# TK512_Optisk_Mottaker.net
KiCad netlist of a schematic drawn in Altium Designer
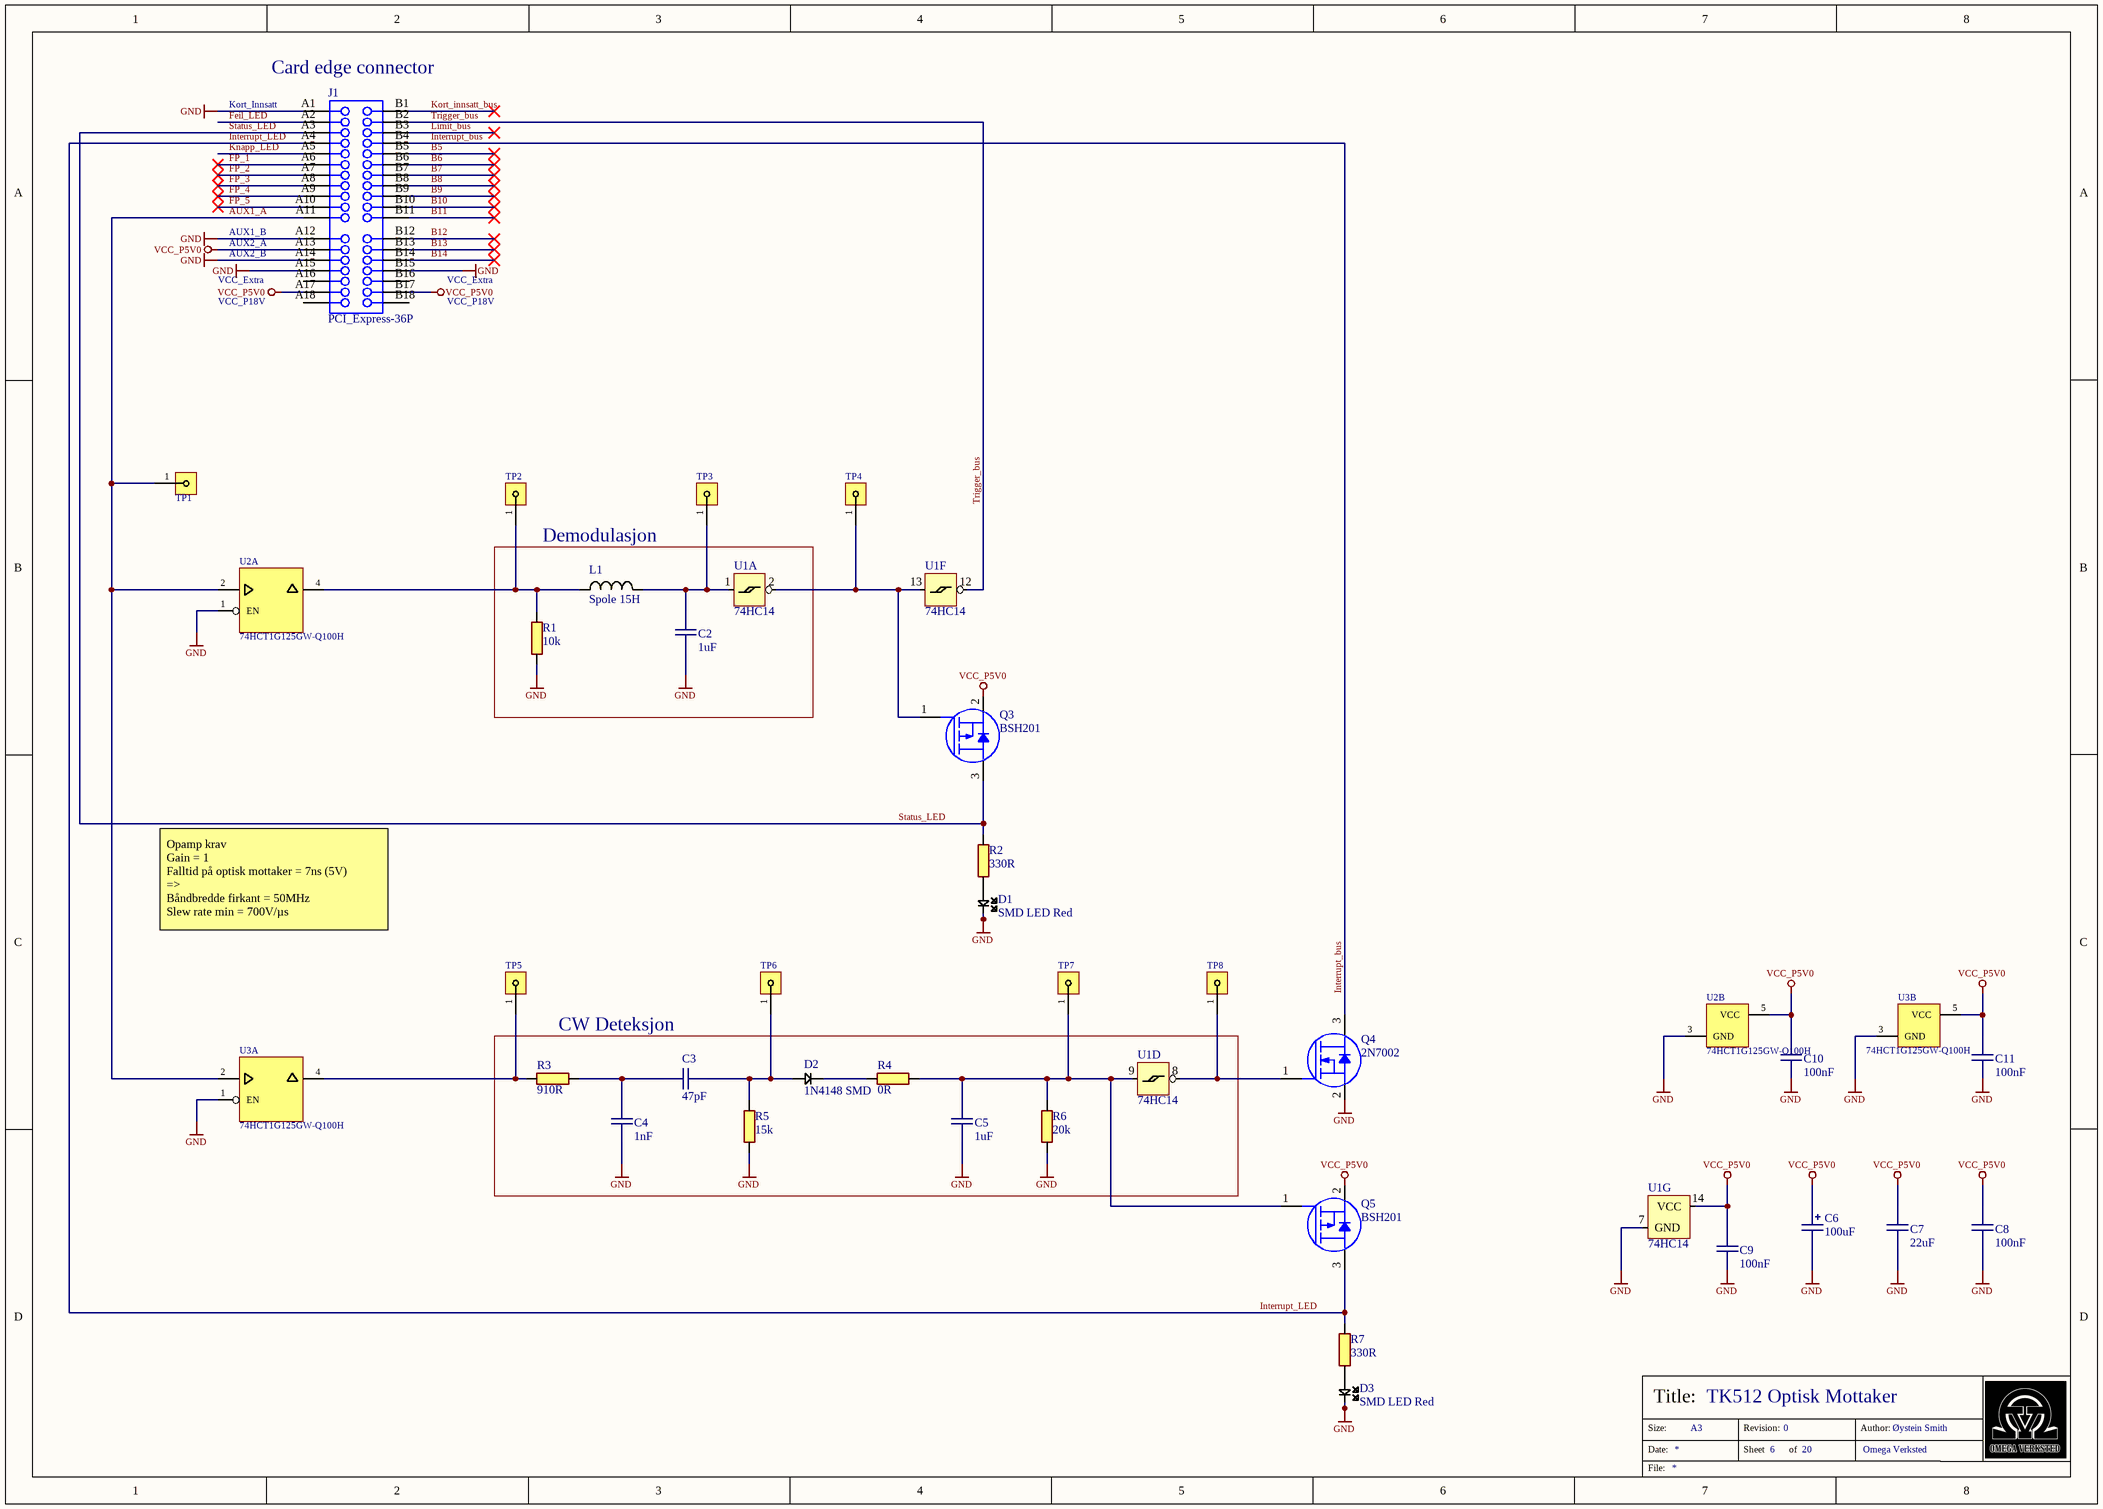
[diagram p0: TK512_Optisk_Mottaker.SchDoc]

(export (version "E")
  (design (tool "Eeschema 10.0.6"))
  (components
    (comp (ref "C2")
      (value "1uF")
      (footprint "CAPC1206(3216)170_N")
      (description "X7R 50V")
      (libsource (lib "OVLib_64") (part "CAP"))
    )
    (comp (ref "C3")
      (value "47pF")
      (footprint "CAPC0603(1608)55_N")
      (description "NP0 50V 5%")
      (libsource (lib "OVLib_64") (part "CAP"))
    )
    (comp (ref "C4")
      (value "1nF")
      (footprint "CAPC0603(1608)55_N")
      (description "X7R 50V 5%")
      (libsource (lib "OVLib_64") (part "CAP"))
    )
    (comp (ref "C5")
      (value "1uF")
      (footprint "CAPC0805(2012)100_N")
      (description "X7R 50V 10%")
      (libsource (lib "OVLib_64") (part "CAP"))
    )
    (comp (ref "C6")
      (value "100uF")
      (footprint "CAPPR25D06H11")
      (description "25V 2.5mm pitch")
      (libsource (lib "OVLib_64") (part "POLCAP"))
    )
    (comp (ref "C7")
      (value "22uF")
      (footprint "CAPC1206(3216)170_N")
      (description "10V 10% Tantalum")
      (libsource (lib "OVLib_64") (part "CAP"))
    )
    (comp (ref "C8")
      (value "100nF")
      (footprint "CAPC0603(1608)55_N")
      (description "X7R 50V 5%")
      (libsource (lib "OVLib_64") (part "CAP"))
    )
    (comp (ref "C9")
      (value "100nF")
      (footprint "CAPC0603(1608)55_N")
      (description "X7R 50V 5%")
      (libsource (lib "OVLib_64") (part "CAP"))
    )
    (comp (ref "C10")
      (value "100nF")
      (footprint "CAPC0603(1608)55_N")
      (description "X7R 50V 5%")
      (libsource (lib "OVLib_64") (part "CAP"))
    )
    (comp (ref "C11")
      (value "100nF")
      (footprint "CAPC0603(1608)55_N")
      (description "X7R 50V 5%")
      (libsource (lib "OVLib_64") (part "CAP"))
    )
    (comp (ref "D1")
      (value "SMD LED Red")
      (footprint "I_LEDC0603(1608)_N")
      (description "SMD")
      (libsource (lib "OVLib_64") (part "LED"))
    )
    (comp (ref "D2")
      (value "1N4148 SMD")
      (footprint "SOD123")
      (description "SMD signaldiode")
      (libsource (lib "OVLib_64") (part "Diode"))
    )
    (comp (ref "D3")
      (value "SMD LED Red")
      (footprint "I_LEDC0603(1608)_N")
      (description "SMD")
      (libsource (lib "OVLib_64") (part "LED"))
    )
    (comp (ref "J1")
      (value "PCI_Express-36P")
      (footprint "PCIeX1-GF-2D-1000-1K-O36")
      (description "PCI express PCB kortkankonnektor")
      (libsource (lib "OVLib_64") (part "PCI_Express-36P"))
    )
    (comp (ref "L1")
      (value "Spole 15H")
      (footprint "INDP3225X20N")
      (description "Wirewound Inductor, 15 µH, 2.8 ohm, 20 MHz, 130 mA")
      (libsource (lib "OVLib_64") (part "IND_GENERIC"))
    )
    (comp (ref "Q3")
      (value "BSH201")
      (footprint "SOT23-3_N")
      (description "P-Channel MOSFET 300mA")
      (libsource (lib "OVLib_64") (part "MOSFET_P_GSD"))
    )
    (comp (ref "Q4")
      (value "2N7002")
      (footprint "SOT323_N")
      (description "N-Channel MOSFET 300mA")
      (libsource (lib "OVLib_64") (part "MOSFET_N_GSD"))
    )
    (comp (ref "Q5")
      (value "BSH201")
      (footprint "SOT23-3_N")
      (description "P-Channel MOSFET 300mA")
      (libsource (lib "OVLib_64") (part "MOSFET_P_GSD"))
    )
    (comp (ref "R1")
      (value "10k")
      (footprint "RESC0603(1608)_N")
      (description "0.1W 1% Thick film resistor")
      (libsource (lib "") (part "Resistor2_2"))
    )
    (comp (ref "R2")
      (value "330R")
      (footprint "RESC0603(1608)_N")
      (description "0.1W 1% Thick film resistor")
      (libsource (lib "OVLib_64") (part "Resistor2"))
    )
    (comp (ref "R3")
      (value "910R")
      (footprint "RESC0603(1608)_N")
      (description "0.1W 1% Thick film resistor")
      (libsource (lib "") (part "Resistor2_1"))
    )
    (comp (ref "R4")
      (value "0R")
      (footprint "RESC0603(1608)_N")
      (description "0.1W 1% Thick film resistor, Jumper")
      (libsource (lib "") (part "Resistor2_1"))
    )
    (comp (ref "R5")
      (value "15k")
      (footprint "RESC0603(1608)_N")
      (description "0.1W 1% Thick film resistor")
      (libsource (lib "OVLib_64") (part "Resistor2"))
    )
    (comp (ref "R6")
      (value "20k")
      (footprint "RESC0603(1608)_N")
      (description "0.1W 1% Thick film resistor")
      (libsource (lib "OVLib_64") (part "Resistor2"))
    )
    (comp (ref "R7")
      (value "330R")
      (footprint "RESC0603(1608)_N")
      (description "0.1W 1% Thick film resistor")
      (libsource (lib "OVLib_64") (part "Resistor2"))
    )
    (comp (ref "TP1")
      (value "Header1x1")
      (footprint "HDRV1W64P254_1X1_254X254X900B")
      (description "2,54mm pitch")
      (libsource (lib "") (part "Header1x1_1"))
    )
    (comp (ref "TP2")
      (value "Header1x1")
      (footprint "HDRV1W64P254_1X1_254X254X900B")
      (description "2,54mm pitch")
      (libsource (lib "OVLib_64") (part "Header1x1"))
    )
    (comp (ref "TP3")
      (value "Header1x1")
      (footprint "HDRV1W64P254_1X1_254X254X900B")
      (description "2,54mm pitch")
      (libsource (lib "OVLib_64") (part "Header1x1"))
    )
    (comp (ref "TP4")
      (value "Header1x1")
      (footprint "HDRV1W64P254_1X1_254X254X900B")
      (description "2,54mm pitch")
      (libsource (lib "OVLib_64") (part "Header1x1"))
    )
    (comp (ref "TP5")
      (value "Header1x1")
      (footprint "HDRV1W64P254_1X1_254X254X900B")
      (description "2,54mm pitch")
      (libsource (lib "OVLib_64") (part "Header1x1"))
    )
    (comp (ref "TP6")
      (value "Header1x1")
      (footprint "HDRV1W64P254_1X1_254X254X900B")
      (description "2,54mm pitch")
      (libsource (lib "OVLib_64") (part "Header1x1"))
    )
    (comp (ref "TP7")
      (value "Header1x1")
      (footprint "HDRV1W64P254_1X1_254X254X900B")
      (description "2,54mm pitch")
      (libsource (lib "OVLib_64") (part "Header1x1"))
    )
    (comp (ref "TP8")
      (value "Header1x1")
      (footprint "HDRV1W64P254_1X1_254X254X900B")
      (description "2,54mm pitch")
      (libsource (lib "OVLib_64") (part "Header1x1"))
    )
    (comp (ref "U1")
      (value "74HC14")
      (footprint "SOIC-14")
      (description "Hex Schmitt trigger")
      (libsource (lib "OVLib_64") (part "6XSchmidt-Trigger"))
    )
    (comp (ref "U2")
      (value "74HCT1G125GW-Q100H")
      (footprint "SOT95P285X110-5N")
      (description "Buffer / Line Driver, 74HCT1G125, 4.5 V to 5.5 V, TSSOP-5")
      (libsource (lib "OVLib_64") (part "74HC1G125-Q100"))
    )
    (comp (ref "U3")
      (value "74HCT1G125GW-Q100H")
      (footprint "SOT95P285X110-5N")
      (description "Buffer / Line Driver, 74HCT1G125, 4.5 V to 5.5 V, TSSOP-5")
      (libsource (lib "OVLib_64") (part "74HC1G125-Q100"))
    )
  )
  (nets
    (net (code "1") (name "/AUX1_A") (class "Default")
      (node (ref "J1") (pin "A11") (pinfunction "A11_A11") (pintype "passive"))
      (node (ref "TP1") (pin "1") (pinfunction "1_1") (pintype "passive"))
      (node (ref "U2") (pin "2") (pinfunction "IN_2") (pintype "passive"))
      (node (ref "U3") (pin "2") (pinfunction "IN_2") (pintype "passive"))
    )
    (net (code "2") (name "/B5") (class "Default")
      (node (ref "J1") (pin "B5") (pinfunction "B5_B5") (pintype "passive+no_connect"))
    )
    (net (code "3") (name "/B6") (class "Default")
      (node (ref "J1") (pin "B6") (pinfunction "B6_B6") (pintype "passive+no_connect"))
    )
    (net (code "4") (name "/B7") (class "Default")
      (node (ref "J1") (pin "B7") (pinfunction "B7_B7") (pintype "passive+no_connect"))
    )
    (net (code "5") (name "/B8") (class "Default")
      (node (ref "J1") (pin "B8") (pinfunction "B8_B8") (pintype "passive+no_connect"))
    )
    (net (code "6") (name "/B9") (class "Default")
      (node (ref "J1") (pin "B9") (pinfunction "B9_B9") (pintype "passive+no_connect"))
    )
    (net (code "7") (name "/B10") (class "Default")
      (node (ref "J1") (pin "B10") (pinfunction "B10_B10") (pintype "passive+no_connect"))
    )
    (net (code "8") (name "/B11") (class "Default")
      (node (ref "J1") (pin "B11") (pinfunction "B11_B11") (pintype "passive+no_connect"))
    )
    (net (code "9") (name "/B12") (class "Default")
      (node (ref "J1") (pin "B12") (pinfunction "B12_B12") (pintype "passive+no_connect"))
    )
    (net (code "10") (name "/B13") (class "Default")
      (node (ref "J1") (pin "B13") (pinfunction "B13_B13") (pintype "passive+no_connect"))
    )
    (net (code "11") (name "/B14") (class "Default")
      (node (ref "J1") (pin "B14") (pinfunction "B14_B14") (pintype "passive+no_connect"))
    )
    (net (code "12") (name "/FP_1") (class "Default")
      (node (ref "J1") (pin "A6") (pinfunction "A6_A6") (pintype "passive+no_connect"))
    )
    (net (code "13") (name "/FP_2") (class "Default")
      (node (ref "J1") (pin "A7") (pinfunction "A7_A7") (pintype "passive+no_connect"))
    )
    (net (code "14") (name "/FP_3") (class "Default")
      (node (ref "J1") (pin "A8") (pinfunction "A8_A8") (pintype "passive+no_connect"))
    )
    (net (code "15") (name "/FP_4") (class "Default")
      (node (ref "J1") (pin "A9") (pinfunction "A9_A9") (pintype "passive+no_connect"))
    )
    (net (code "16") (name "/FP_5") (class "Default")
      (node (ref "J1") (pin "A10") (pinfunction "A10_A10") (pintype "passive+no_connect"))
    )
    (net (code "17") (name "/Feil_LED") (class "Default")
      (node (ref "J1") (pin "A2") (pinfunction "A2_A2") (pintype "passive"))
    )
    (net (code "18") (name "/Interrupt_LED") (class "Default")
      (node (ref "J1") (pin "A4") (pinfunction "A4_A4") (pintype "passive"))
      (node (ref "Q5") (pin "3") (pinfunction "Drain_3") (pintype "passive"))
      (node (ref "R7") (pin "2") (pinfunction "2_2") (pintype "passive"))
    )
    (net (code "19") (name "/Interrupt_bus") (class "Default")
      (node (ref "J1") (pin "B4") (pinfunction "B4_B4") (pintype "passive"))
      (node (ref "Q4") (pin "3") (pinfunction "Drain_3") (pintype "passive"))
    )
    (net (code "20") (name "/Knapp_LED") (class "Default")
      (node (ref "J1") (pin "A5") (pinfunction "A5_A5") (pintype "passive"))
    )
    (net (code "21") (name "/Kort_innsatt_bus") (class "Default")
      (node (ref "J1") (pin "B1") (pinfunction "B1_B1") (pintype "passive+no_connect"))
    )
    (net (code "22") (name "/Limit_bus") (class "Default")
      (node (ref "J1") (pin "B3") (pinfunction "B3_B3") (pintype "passive+no_connect"))
    )
    (net (code "23") (name "/Status_LED") (class "Default")
      (node (ref "J1") (pin "A3") (pinfunction "A3_A3") (pintype "passive"))
      (node (ref "Q3") (pin "3") (pinfunction "Drain_3") (pintype "passive"))
      (node (ref "R2") (pin "2") (pinfunction "2_2") (pintype "passive"))
    )
    (net (code "24") (name "/Trigger_bus") (class "Default")
      (node (ref "J1") (pin "B2") (pinfunction "B2_B2") (pintype "passive"))
      (node (ref "U1") (pin "12") (pinfunction "12_12") (pintype "passive"))
    )
    (net (code "25") (name "GND") (class "Default")
      (node (ref "C10") (pin "1") (pinfunction "1_1") (pintype "passive"))
      (node (ref "C11") (pin "1") (pinfunction "1_1") (pintype "passive"))
      (node (ref "C2") (pin "1") (pinfunction "1_1") (pintype "passive"))
      (node (ref "C4") (pin "1") (pinfunction "1_1") (pintype "passive"))
      (node (ref "C5") (pin "1") (pinfunction "1_1") (pintype "passive"))
      (node (ref "C6") (pin "1") (pinfunction "1_1") (pintype "passive"))
      (node (ref "C7") (pin "1") (pinfunction "1_1") (pintype "passive"))
      (node (ref "C8") (pin "1") (pinfunction "1_1") (pintype "passive"))
      (node (ref "C9") (pin "1") (pinfunction "1_1") (pintype "passive"))
      (node (ref "D1") (pin "2") (pinfunction "2_2") (pintype "passive"))
      (node (ref "D3") (pin "2") (pinfunction "2_2") (pintype "passive"))
      (node (ref "J1") (pin "A1") (pinfunction "A1_A1") (pintype "passive"))
      (node (ref "J1") (pin "A12") (pinfunction "A12_A12") (pintype "passive"))
      (node (ref "J1") (pin "A14") (pinfunction "A14_A14") (pintype "passive"))
      (node (ref "J1") (pin "A15") (pinfunction "A15_A15") (pintype "passive"))
      (node (ref "J1") (pin "B15") (pinfunction "B15_B15") (pintype "passive"))
      (node (ref "Q4") (pin "2") (pinfunction "Source_2") (pintype "passive"))
      (node (ref "R1") (pin "2") (pinfunction "2_2") (pintype "passive"))
      (node (ref "R5") (pin "1") (pinfunction "1_1") (pintype "passive"))
      (node (ref "R6") (pin "1") (pinfunction "1_1") (pintype "passive"))
      (node (ref "U1") (pin "7") (pinfunction "GND_7") (pintype "passive"))
      (node (ref "U2") (pin "1") (pinfunction "EN_1") (pintype "passive"))
      (node (ref "U2") (pin "3") (pinfunction "GND_3") (pintype "passive"))
      (node (ref "U3") (pin "1") (pinfunction "EN_1") (pintype "passive"))
      (node (ref "U3") (pin "3") (pinfunction "GND_3") (pintype "passive"))
    )
    (net (code "26") (name "Net-(C2-Pad2)") (class "Default")
      (node (ref "C2") (pin "2") (pinfunction "2_2") (pintype "passive"))
      (node (ref "L1") (pin "2") (pinfunction "2_2") (pintype "passive"))
      (node (ref "TP3") (pin "1") (pinfunction "1_1") (pintype "passive"))
      (node (ref "U1") (pin "1") (pinfunction "1_1") (pintype "passive"))
    )
    (net (code "27") (name "Net-(C3-Pad2)") (class "Default")
      (node (ref "C3") (pin "2") (pinfunction "2_2") (pintype "passive"))
      (node (ref "C4") (pin "2") (pinfunction "2_2") (pintype "passive"))
      (node (ref "R3") (pin "2") (pinfunction "2_2") (pintype "passive"))
    )
    (net (code "28") (name "Net-(D1-Pad1)") (class "Default")
      (node (ref "D1") (pin "1") (pinfunction "1_1") (pintype "passive"))
      (node (ref "R2") (pin "1") (pinfunction "1_1") (pintype "passive"))
    )
    (net (code "29") (name "Net-(D2-A)") (class "Default")
      (node (ref "C3") (pin "1") (pinfunction "1_1") (pintype "passive"))
      (node (ref "D2") (pin "1") (pinfunction "A_1") (pintype "passive"))
      (node (ref "R5") (pin "2") (pinfunction "2_2") (pintype "passive"))
      (node (ref "TP6") (pin "1") (pinfunction "1_1") (pintype "passive"))
    )
    (net (code "30") (name "Net-(D2-K)") (class "Default")
      (node (ref "D2") (pin "2") (pinfunction "K_2") (pintype "passive"))
      (node (ref "R4") (pin "1") (pinfunction "1_1") (pintype "passive"))
    )
    (net (code "31") (name "Net-(D3-Pad1)") (class "Default")
      (node (ref "D3") (pin "1") (pinfunction "1_1") (pintype "passive"))
      (node (ref "R7") (pin "1") (pinfunction "1_1") (pintype "passive"))
    )
    (net (code "32") (name "Net-(Q3-Gate)") (class "Default")
      (node (ref "Q3") (pin "1") (pinfunction "Gate_1") (pintype "passive"))
      (node (ref "TP4") (pin "1") (pinfunction "1_1") (pintype "passive"))
      (node (ref "U1") (pin "13") (pinfunction "13_13") (pintype "passive"))
      (node (ref "U1") (pin "2") (pinfunction "2_2") (pintype "passive"))
    )
    (net (code "33") (name "Net-(Q4-Gate)") (class "Default")
      (node (ref "Q4") (pin "1") (pinfunction "Gate_1") (pintype "passive"))
      (node (ref "TP8") (pin "1") (pinfunction "1_1") (pintype "passive"))
      (node (ref "U1") (pin "8") (pinfunction "8_8") (pintype "passive"))
    )
    (net (code "34") (name "Net-(Q5-Gate)") (class "Default")
      (node (ref "C5") (pin "2") (pinfunction "2_2") (pintype "passive"))
      (node (ref "Q5") (pin "1") (pinfunction "Gate_1") (pintype "passive"))
      (node (ref "R4") (pin "2") (pinfunction "2_2") (pintype "passive"))
      (node (ref "R6") (pin "2") (pinfunction "2_2") (pintype "passive"))
      (node (ref "TP7") (pin "1") (pinfunction "1_1") (pintype "passive"))
      (node (ref "U1") (pin "9") (pinfunction "9_9") (pintype "passive"))
    )
    (net (code "35") (name "Net-(U2A-OUT)") (class "Default")
      (node (ref "L1") (pin "1") (pinfunction "1_1") (pintype "passive"))
      (node (ref "R1") (pin "1") (pinfunction "1_1") (pintype "passive"))
      (node (ref "TP2") (pin "1") (pinfunction "1_1") (pintype "passive"))
      (node (ref "U2") (pin "4") (pinfunction "OUT_4") (pintype "passive"))
    )
    (net (code "36") (name "Net-(U3A-OUT)") (class "Default")
      (node (ref "R3") (pin "1") (pinfunction "1_1") (pintype "passive"))
      (node (ref "TP5") (pin "1") (pinfunction "1_1") (pintype "passive"))
      (node (ref "U3") (pin "4") (pinfunction "OUT_4") (pintype "passive"))
    )
    (net (code "37") (name "VCC_P5V0") (class "Default")
      (node (ref "C10") (pin "2") (pinfunction "2_2") (pintype "passive"))
      (node (ref "C11") (pin "2") (pinfunction "2_2") (pintype "passive"))
      (node (ref "C6") (pin "2") (pinfunction "2_2") (pintype "passive"))
      (node (ref "C7") (pin "2") (pinfunction "2_2") (pintype "passive"))
      (node (ref "C8") (pin "2") (pinfunction "2_2") (pintype "passive"))
      (node (ref "C9") (pin "2") (pinfunction "2_2") (pintype "passive"))
      (node (ref "J1") (pin "A13") (pinfunction "A13_A13") (pintype "passive"))
      (node (ref "J1") (pin "A17") (pinfunction "A17_A17") (pintype "passive"))
      (node (ref "J1") (pin "B17") (pinfunction "B17_B17") (pintype "passive"))
      (node (ref "Q3") (pin "2") (pinfunction "Source_2") (pintype "passive"))
      (node (ref "Q5") (pin "2") (pinfunction "Source_2") (pintype "passive"))
      (node (ref "U1") (pin "14") (pinfunction "VCC_14") (pintype "passive"))
      (node (ref "U2") (pin "5") (pinfunction "VCC_5") (pintype "passive"))
      (node (ref "U3") (pin "5") (pinfunction "VCC_5") (pintype "passive"))
    )
    (net (code "38") (name "unconnected-(J1-PadA16)") (class "Default")
      (node (ref "J1") (pin "A16") (pinfunction "A16_A16") (pintype "passive"))
    )
    (net (code "39") (name "unconnected-(J1-PadA18)") (class "Default")
      (node (ref "J1") (pin "A18") (pinfunction "A18_A18") (pintype "passive"))
    )
    (net (code "40") (name "unconnected-(J1-PadB16)") (class "Default")
      (node (ref "J1") (pin "B16") (pinfunction "B16_B16") (pintype "passive"))
    )
    (net (code "41") (name "unconnected-(J1-PadB18)") (class "Default")
      (node (ref "J1") (pin "B18") (pinfunction "B18_B18") (pintype "passive"))
    )
  )
)
